# openSX70_ALPHA_V6-2-4-20181127.net
KiCad netlist of a schematic drawn in EAGLE
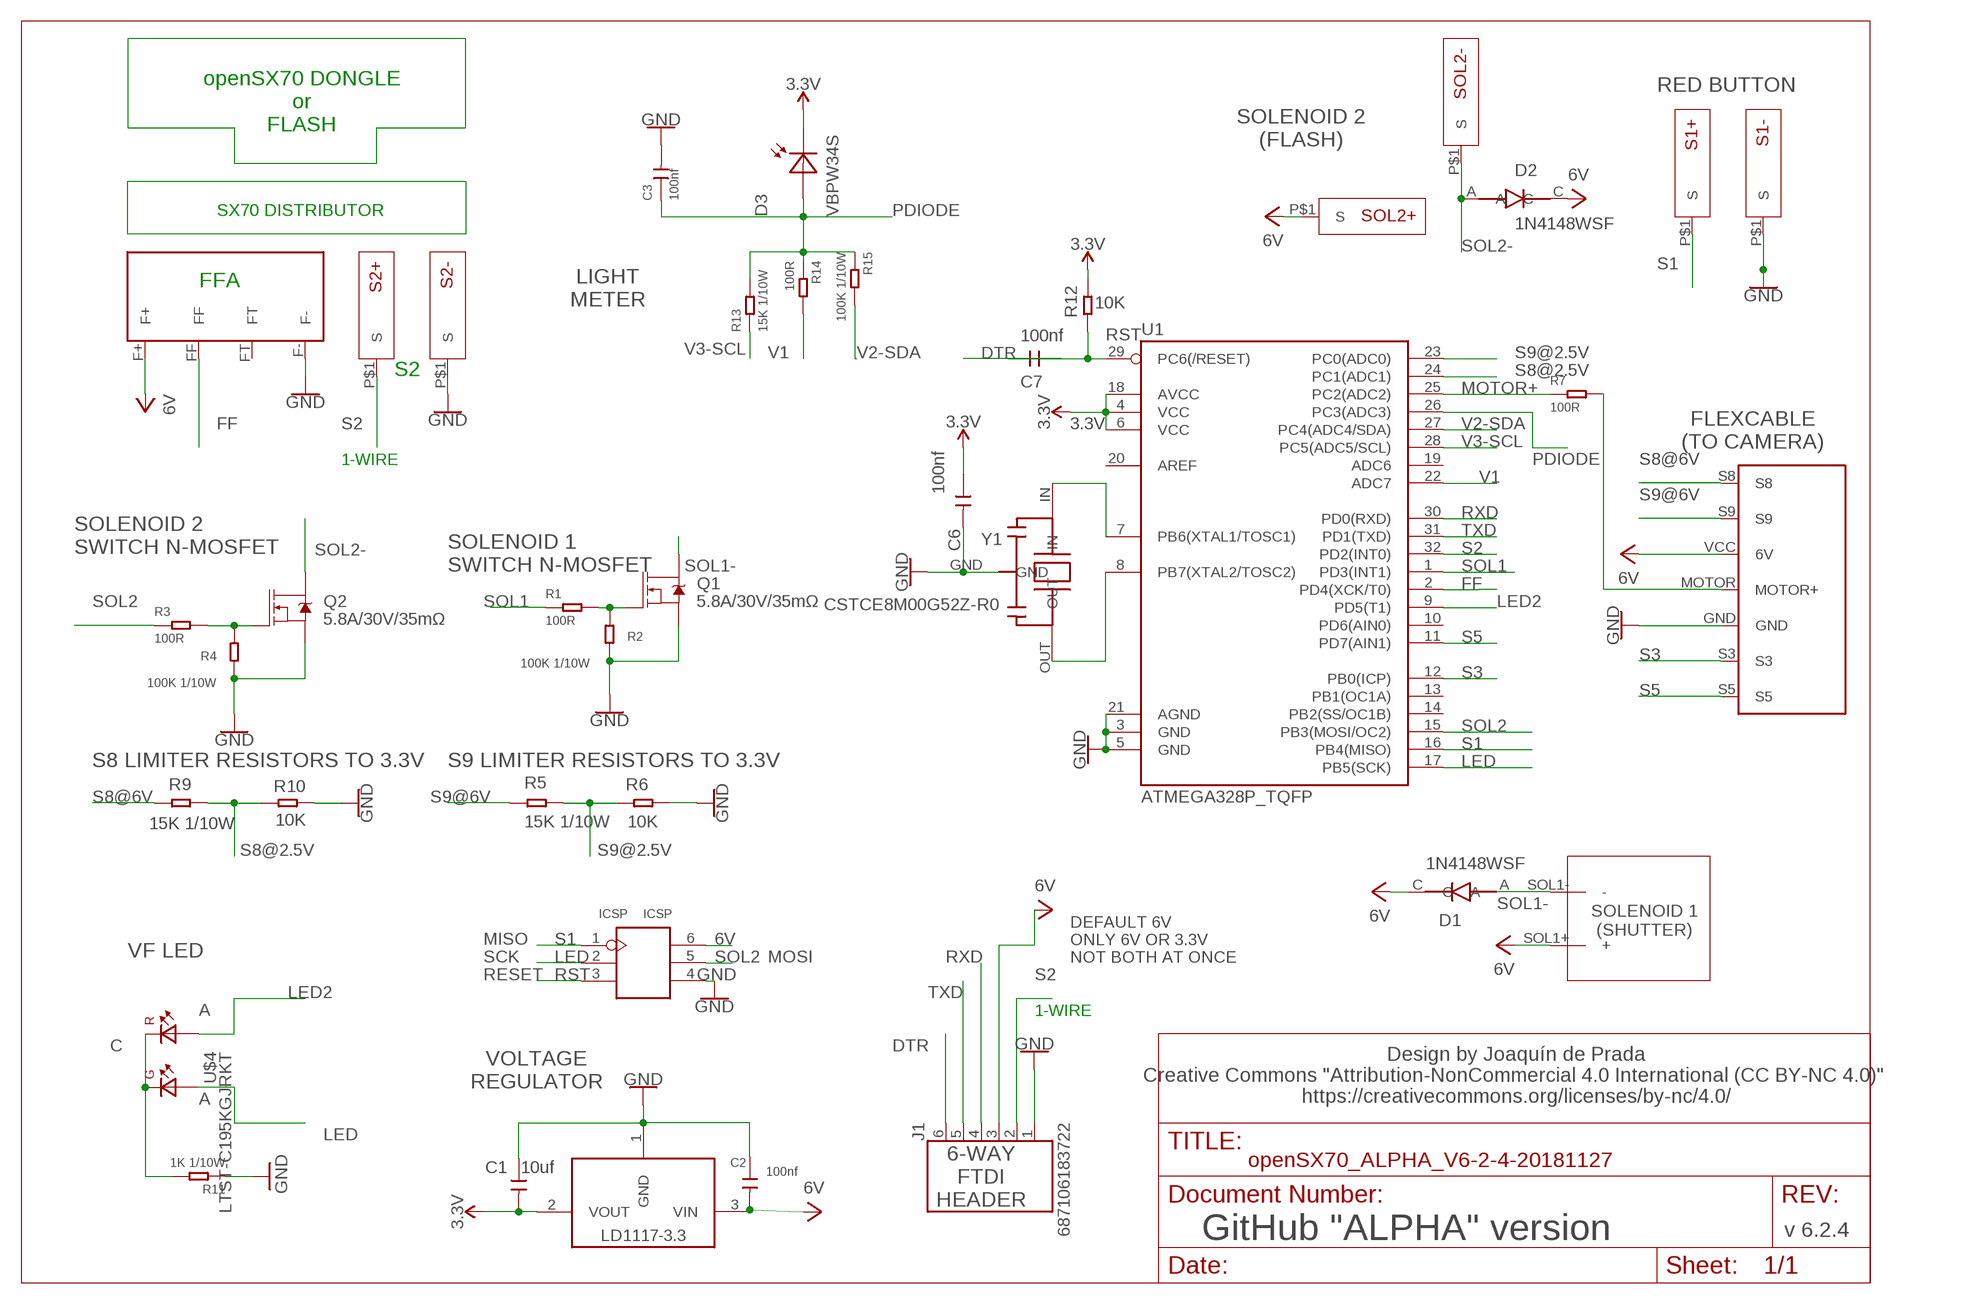
[diagram p0: schematic, sheet 1]

(export (version "E")
  (design (tool "Eeschema 10.0.6"))
  (components
    (comp (ref "C1")
      (value "10uf")
      (footprint "eagle-import:C0603")
      (fields (field (name "MPN") "CC0603KRX5R6BB106"))
      (libsource (lib "eagle-import") (part "CERAMIC-10UF-10V-10%-X5R(0603)"))
    )
    (comp (ref "C2")
      (value "100nf")
      (footprint "eagle-import:C0603")
      (fields (field (name "MPN") "CC0603KRX7R9BB104"))
      (libsource (lib "eagle-import") (part "CERAMIC-100NF-50V-10%-X7R(0603)"))
    )
    (comp (ref "C3")
      (value "100nf")
      (footprint "eagle-import:C0603")
      (fields (field (name "MPN") "CC0603KRX7R9BB104"))
      (libsource (lib "eagle-import") (part "CERAMIC-100NF-50V-10%-X7R(0603)"))
    )
    (comp (ref "C6")
      (value "100nf")
      (footprint "eagle-import:C0603")
      (fields (field (name "MPN") "CC0603KRX7R9BB104"))
      (libsource (lib "eagle-import") (part "CERAMIC-100NF-50V-10%-X7R(0603)"))
    )
    (comp (ref "C7")
      (value "100nf")
      (footprint "eagle-import:C0603")
      (fields (field (name "MPN") "CC0603KRX7R9BB104"))
      (libsource (lib "eagle-import") (part "CERAMIC-100NF-50V-10%-X7R(0603)"))
    )
    (comp (ref "D1")
      (value "1N4148WSF")
      (footprint "eagle-import:SODFL2512X100N")
      (fields (field (name "MANUFACTURER") "Fairchild Semiconductor"))
      (libsource (lib "eagle-import") (part "1N4148WS"))
    )
    (comp (ref "D2")
      (value "1N4148WSF")
      (footprint "eagle-import:SODFL2512X100N")
      (fields (field (name "MANUFACTURER") "Fairchild Semiconductor"))
      (libsource (lib "eagle-import") (part "1N4148WS"))
    )
    (comp (ref "D3")
      (value "VBPW34S")
      (footprint "eagle-import:SOD6439X130N")
      (fields (field (name "DIGI-KEY_PART_NUMBER") "751-1500-1-ND") (field (name "MF") "Vishay"))
      (libsource (lib "eagle-import") (part "VBPW34S"))
    )
    (comp (ref "ICSP")
      (value "ICSP")
      (footprint "eagle-import:H2X3-2.54")
      (libsource (lib "eagle-import") (part "ICSP"))
    )
    (comp (ref "J1")
      (value "687106183722")
      (footprint "eagle-import:687106183722")
      (fields (field (name "MF") "Wurth Electronics"))
      (libsource (lib "eagle-import") (part "687106183722"))
    )
    (comp (ref "LD11172.5V")
      (value "LD1117 2.5V")
      (footprint "eagle-import:SOT223")
      (fields (field (name "MF") "Advanced Monolithic Systems") (field (name "MP") "AMS1117-5.0"))
      (libsource (lib "eagle-import") (part "LD1117-3.3"))
    )
    (comp (ref "Q1")
      (value "5.8A/30V/35mΩ")
      (footprint "eagle-import:SOT23-3")
      (libsource (lib "eagle-import") (part "MOSFET-NCH-AO3404A"))
    )
    (comp (ref "Q2")
      (value "5.8A/30V/35mΩ")
      (footprint "eagle-import:SOT23-3")
      (libsource (lib "eagle-import") (part "MOSFET-NCH-AO3404A"))
    )
    (comp (ref "R1")
      (value "100R")
      (footprint "eagle-import:R0603")
      (fields (field (name "MPN") "RC0603JR-07100RL"))
      (libsource (lib "eagle-import") (part "SMD-RES-100R-5%-1/10W(0603)"))
    )
    (comp (ref "R2")
      (value "100K 1/10W")
      (footprint "eagle-import:R0603")
      (fields (field (name "MPN") "RC0603JR-07100KL"))
      (libsource (lib "eagle-import") (part "SMD-RES-100K-5%-1/10W(0603)"))
    )
    (comp (ref "R3")
      (value "100R")
      (footprint "eagle-import:R0603")
      (fields (field (name "MPN") "RC0603JR-07100RL"))
      (libsource (lib "eagle-import") (part "SMD-RES-100R-5%-1/10W(0603)"))
    )
    (comp (ref "R4")
      (value "100K 1/10W")
      (footprint "eagle-import:R0603")
      (fields (field (name "MPN") "RC0603JR-07100KL"))
      (libsource (lib "eagle-import") (part "SMD-RES-100K-5%-1/10W(0603)"))
    )
    (comp (ref "R5")
      (value "15K 1/10W")
      (footprint "eagle-import:R0603")
      (fields (field (name "MPN") "RC0603FR-0715KL"))
      (libsource (lib "eagle-import") (part "SMD-RES-15K-1%-1/10W(0603)"))
    )
    (comp (ref "R6")
      (value "10K")
      (footprint "eagle-import:R0603")
      (fields (field (name "MPN") "RC0603FR-0710KL"))
      (libsource (lib "eagle-import") (part "SMD-RES-10K-1%-1/10W(0603)"))
    )
    (comp (ref "R7")
      (value "100R")
      (footprint "eagle-import:R0603")
      (fields (field (name "MPN") "RC0603JR-07100RL"))
      (libsource (lib "eagle-import") (part "SMD-RES-100R-5%-1/10W(0603)"))
    )
    (comp (ref "R9")
      (value "15K 1/10W")
      (footprint "eagle-import:R0603")
      (fields (field (name "MPN") "RC0603FR-0715KL"))
      (libsource (lib "eagle-import") (part "SMD-RES-15K-1%-1/10W(0603)"))
    )
    (comp (ref "R10")
      (value "10K")
      (footprint "eagle-import:R0603")
      (fields (field (name "MPN") "RC0603FR-0710KL"))
      (libsource (lib "eagle-import") (part "SMD-RES-10K-1%-1/10W(0603)"))
    )
    (comp (ref "R11")
      (value "1K 1/10W")
      (footprint "eagle-import:R0603")
      (fields (field (name "MPN") "RC0603JR-071KL"))
      (libsource (lib "eagle-import") (part "SMD-RES-1K-5%-1/10W(0603)"))
    )
    (comp (ref "R12")
      (value "10K")
      (footprint "eagle-import:R0603")
      (fields (field (name "MPN") "RC0603FR-0710KL"))
      (libsource (lib "eagle-import") (part "SMD-RES-10K-1%-1/10W(0603)"))
    )
    (comp (ref "R13")
      (value "15K 1/10W")
      (footprint "eagle-import:R0603")
      (fields (field (name "MPN") "RC0603FR-0715KL"))
      (libsource (lib "eagle-import") (part "SMD-RES-15K-1%-1/10W(0603)"))
    )
    (comp (ref "R14")
      (value "100R")
      (footprint "eagle-import:R0603")
      (fields (field (name "MPN") "RC0603JR-07100RL"))
      (libsource (lib "eagle-import") (part "SMD-RES-100R-5%-1/10W(0603)"))
    )
    (comp (ref "R15")
      (value "100K 1/10W")
      (footprint "eagle-import:R0603")
      (fields (field (name "MPN") "RC0603JR-07100KL"))
      (libsource (lib "eagle-import") (part "SMD-RES-100K-5%-1/10W(0603)"))
    )
    (comp (ref "S1+")
      (value "SX70-S-PAD-NEW")
      (footprint "eagle-import:SX70-S-PAD2")
      (libsource (lib "eagle-import") (part "SX70-S-PAD-NEW"))
    )
    (comp (ref "S1-")
      (value "SX70-S-PAD-NEW")
      (footprint "eagle-import:SX70-S-PAD2")
      (libsource (lib "eagle-import") (part "SX70-S-PAD-NEW"))
    )
    (comp (ref "S2+")
      (value "SX70-S-PAD-NEW")
      (footprint "eagle-import:SX70-S-PAD2")
      (libsource (lib "eagle-import") (part "SX70-S-PAD-NEW"))
    )
    (comp (ref "S2-")
      (value "SX70-S-PAD-NEW")
      (footprint "eagle-import:SX70-S-PAD2")
      (libsource (lib "eagle-import") (part "SX70-S-PAD-NEW"))
    )
    (comp (ref "SOL1")
      (value "SX70-SOLENOID1-2PADS")
      (footprint "eagle-import:SX70-SOLENOID1-2")
      (libsource (lib "eagle-import") (part "SX70-SOLENOID1-2PADS"))
    )
    (comp (ref "SOL2+")
      (value "SX70-S-PAD-NEW")
      (footprint "eagle-import:SX70-S-PAD2")
      (libsource (lib "eagle-import") (part "SX70-S-PAD-NEW"))
    )
    (comp (ref "SOL2-")
      (value "SX70-S-PAD-NEW")
      (footprint "eagle-import:SX70-S-PAD2")
      (libsource (lib "eagle-import") (part "SX70-S-PAD-NEW"))
    )
    (comp (ref "U$1")
      (value "SX70-7-PAD")
      (footprint "eagle-import:SX70-7-PAD-PROPER")
      (libsource (lib "eagle-import") (part "SX70-7-PAD"))
    )
    (comp (ref "U$2")
      (value "FFA")
      (footprint "eagle-import:FFA-PAD-PACKAGE")
      (libsource (lib "eagle-import") (part "SX70-FFA-PAD"))
    )
    (comp (ref "U$4")
      (value "LTST-C195KGJRKT")
      (footprint "eagle-import:LTST-BILED-15X16")
      (fields (field (name "MF") "Lite-On Inc."))
      (libsource (lib "eagle-import") (part "LTST-C195KGJRKT"))
    )
    (comp (ref "U1")
      (value "ATMEGA328P_TQFP")
      (footprint "eagle-import:TQFP32-08")
      (libsource (lib "eagle-import") (part "ATMEGA328P_TQFP"))
    )
    (comp (ref "Y1")
      (value "CSTCE8M00G52Z-R0")
      (footprint "eagle-import:CFP95P160X100-3N")
      (fields (field (name "MF") "Murata") (field (name "MP") "CSTCE16M0V53-R0"))
      (libsource (lib "eagle-import") (part "CSTCE16M0V53-R0"))
    )
  )
  (nets
    (net (code "1") (name "/DTR") (class "Default")
      (node (ref "C7") (pin "1") (pinfunction "1_1") (pintype "passive"))
      (node (ref "J1") (pin "6") (pinfunction "1_6") (pintype "passive"))
    )
    (net (code "2") (name "/FF") (class "Default")
      (node (ref "U$2") (pin "FF") (pinfunction "FF_FF") (pintype "bidirectional"))
      (node (ref "U1") (pin "2") (pinfunction "PD4(XCK/T0)_2") (pintype "bidirectional"))
    )
    (net (code "3") (name "/LED") (class "Default")
      (node (ref "ICSP") (pin "2") (pinfunction "SCK_2") (pintype "bidirectional"))
      (node (ref "U$4") (pin "P$1") (pinfunction "A1_P$1") (pintype "passive"))
      (node (ref "U1") (pin "17") (pinfunction "PB5(SCK)_17") (pintype "bidirectional"))
    )
    (net (code "4") (name "/LED2") (class "Default")
      (node (ref "U$4") (pin "P$2") (pinfunction "A2_P$2") (pintype "passive"))
      (node (ref "U1") (pin "9") (pinfunction "PD5(T1)_9") (pintype "bidirectional"))
    )
    (net (code "5") (name "/MOTOR+") (class "Default")
      (node (ref "R7") (pin "1") (pinfunction "1_1") (pintype "passive"))
      (node (ref "U1") (pin "25") (pinfunction "PC2(ADC2)_25") (pintype "bidirectional"))
    )
    (net (code "6") (name "/PDIODE") (class "Default")
      (node (ref "C3") (pin "1") (pinfunction "1_1") (pintype "passive"))
      (node (ref "D3") (pin "A") (pinfunction "A_A") (pintype "passive"))
      (node (ref "R13") (pin "2") (pinfunction "2_2") (pintype "passive"))
      (node (ref "R14") (pin "1") (pinfunction "1_1") (pintype "passive"))
      (node (ref "R15") (pin "1") (pinfunction "1_1") (pintype "passive"))
      (node (ref "U1") (pin "26") (pinfunction "PC3(ADC3)_26") (pintype "bidirectional"))
    )
    (net (code "7") (name "/RST") (class "Default")
      (node (ref "C7") (pin "2") (pinfunction "2_2") (pintype "passive"))
      (node (ref "ICSP") (pin "3") (pinfunction "RST_3") (pintype "bidirectional"))
      (node (ref "R12") (pin "1") (pinfunction "1_1") (pintype "passive"))
      (node (ref "U1") (pin "29") (pinfunction "PC6(/RESET)_29") (pintype "bidirectional"))
    )
    (net (code "8") (name "/RXD") (class "Default")
      (node (ref "J1") (pin "4") (pinfunction "3_4") (pintype "passive"))
      (node (ref "U1") (pin "30") (pinfunction "PD0(RXD)_30") (pintype "bidirectional"))
    )
    (net (code "9") (name "/S1") (class "Default")
      (node (ref "ICSP") (pin "1") (pinfunction "MISO_1") (pintype "bidirectional"))
      (node (ref "S1+") (pin "P$1") (pinfunction "S_P$1") (pintype "bidirectional"))
      (node (ref "U1") (pin "16") (pinfunction "PB4(MISO)_16") (pintype "bidirectional"))
    )
    (net (code "10") (name "/S2") (class "Default")
      (node (ref "J1") (pin "2") (pinfunction "5_2") (pintype "passive"))
      (node (ref "S2+") (pin "P$1") (pinfunction "S_P$1") (pintype "bidirectional"))
      (node (ref "U1") (pin "32") (pinfunction "PD2(INT0)_32") (pintype "bidirectional"))
    )
    (net (code "11") (name "/S3") (class "Default")
      (node (ref "U$1") (pin "S3") (pinfunction "S3_S3") (pintype "bidirectional"))
      (node (ref "U1") (pin "12") (pinfunction "PB0(ICP)_12") (pintype "bidirectional"))
    )
    (net (code "12") (name "/S5") (class "Default")
      (node (ref "U$1") (pin "S5") (pinfunction "S5_S5") (pintype "bidirectional"))
      (node (ref "U1") (pin "11") (pinfunction "PD7(AIN1)_11") (pintype "bidirectional"))
    )
    (net (code "13") (name "/S8@2.5V") (class "Default")
      (node (ref "R10") (pin "1") (pinfunction "1_1") (pintype "passive"))
      (node (ref "R9") (pin "2") (pinfunction "2_2") (pintype "passive"))
      (node (ref "U1") (pin "24") (pinfunction "PC1(ADC1)_24") (pintype "bidirectional"))
    )
    (net (code "14") (name "/S8@6V") (class "Default")
      (node (ref "R9") (pin "1") (pinfunction "1_1") (pintype "passive"))
      (node (ref "U$1") (pin "S8") (pinfunction "S8_S8") (pintype "bidirectional"))
    )
    (net (code "15") (name "/S9@2.5V") (class "Default")
      (node (ref "R5") (pin "2") (pinfunction "2_2") (pintype "passive"))
      (node (ref "R6") (pin "1") (pinfunction "1_1") (pintype "passive"))
      (node (ref "U1") (pin "23") (pinfunction "PC0(ADC0)_23") (pintype "bidirectional"))
    )
    (net (code "16") (name "/S9@6V") (class "Default")
      (node (ref "R5") (pin "1") (pinfunction "1_1") (pintype "passive"))
      (node (ref "U$1") (pin "S9") (pinfunction "S9_S9") (pintype "bidirectional"))
    )
    (net (code "17") (name "/SOL1") (class "Default")
      (node (ref "R1") (pin "1") (pinfunction "1_1") (pintype "passive"))
      (node (ref "U1") (pin "1") (pinfunction "PD3(INT1)_1") (pintype "bidirectional"))
    )
    (net (code "18") (name "/SOL1-") (class "Default")
      (node (ref "D1") (pin "A") (pinfunction "A_A") (pintype "passive"))
      (node (ref "Q1") (pin "3") (pinfunction "D_3") (pintype "bidirectional"))
      (node (ref "SOL1") (pin "SOL1-") (pinfunction "-_SOL1-") (pintype "bidirectional"))
    )
    (net (code "19") (name "/SOL2") (class "Default")
      (node (ref "ICSP") (pin "5") (pinfunction "MOSI_5") (pintype "bidirectional"))
      (node (ref "R3") (pin "1") (pinfunction "1_1") (pintype "passive"))
      (node (ref "U1") (pin "15") (pinfunction "PB3(MOSI/OC2)_15") (pintype "bidirectional"))
    )
    (net (code "20") (name "/SOL2-") (class "Default")
      (node (ref "D2") (pin "A") (pinfunction "A_A") (pintype "passive"))
      (node (ref "Q2") (pin "3") (pinfunction "D_3") (pintype "bidirectional"))
      (node (ref "SOL2-") (pin "P$1") (pinfunction "S_P$1") (pintype "bidirectional"))
    )
    (net (code "21") (name "/TXD") (class "Default")
      (node (ref "J1") (pin "5") (pinfunction "2_5") (pintype "passive"))
      (node (ref "U1") (pin "31") (pinfunction "PD1(TXD)_31") (pintype "bidirectional"))
    )
    (net (code "22") (name "/V1") (class "Default")
      (node (ref "R14") (pin "2") (pinfunction "2_2") (pintype "passive"))
      (node (ref "U1") (pin "22") (pinfunction "ADC7_22") (pintype "bidirectional"))
    )
    (net (code "23") (name "/V2-SDA") (class "Default")
      (node (ref "R15") (pin "2") (pinfunction "2_2") (pintype "passive"))
      (node (ref "U1") (pin "27") (pinfunction "PC4(ADC4/SDA)_27") (pintype "bidirectional"))
    )
    (net (code "24") (name "/V3-SCL") (class "Default")
      (node (ref "R13") (pin "1") (pinfunction "1_1") (pintype "passive"))
      (node (ref "U1") (pin "28") (pinfunction "PC5(ADC5/SCL)_28") (pintype "bidirectional"))
    )
    (net (code "25") (name "3.3V") (class "Default")
      (node (ref "C1") (pin "2") (pinfunction "2_2") (pintype "passive"))
      (node (ref "C6") (pin "1") (pinfunction "1_1") (pintype "passive"))
      (node (ref "D3") (pin "C") (pinfunction "C_C") (pintype "passive"))
      (node (ref "LD11172.5V") (pin "2") (pinfunction "VOUT_2") (pintype "bidirectional"))
      (node (ref "R12") (pin "2") (pinfunction "2_2") (pintype "passive"))
      (node (ref "U1") (pin "18") (pinfunction "AVCC_18") (pintype "bidirectional"))
      (node (ref "U1") (pin "4") (pinfunction "VCC_4") (pintype "bidirectional"))
      (node (ref "U1") (pin "6") (pinfunction "VCC_6") (pintype "bidirectional"))
    )
    (net (code "26") (name "6V") (class "Default")
      (node (ref "C2") (pin "2") (pinfunction "2_2") (pintype "passive"))
      (node (ref "D1") (pin "C") (pinfunction "C_C") (pintype "passive"))
      (node (ref "D2") (pin "C") (pinfunction "C_C") (pintype "passive"))
      (node (ref "ICSP") (pin "6") (pinfunction "VCC_6") (pintype "bidirectional"))
      (node (ref "J1") (pin "3") (pinfunction "4_3") (pintype "passive"))
      (node (ref "LD11172.5V") (pin "3") (pinfunction "VIN_3") (pintype "bidirectional"))
      (node (ref "SOL1") (pin "SOL1+") (pinfunction "+_SOL1+") (pintype "bidirectional"))
      (node (ref "SOL2+") (pin "P$1") (pinfunction "S_P$1") (pintype "bidirectional"))
      (node (ref "U$1") (pin "VCC") (pinfunction "6V_VCC") (pintype "bidirectional"))
      (node (ref "U$2") (pin "F+") (pinfunction "F+_F+") (pintype "bidirectional"))
    )
    (net (code "27") (name "GND") (class "Default")
      (node (ref "C1") (pin "1") (pinfunction "1_1") (pintype "passive"))
      (node (ref "C2") (pin "1") (pinfunction "1_1") (pintype "passive"))
      (node (ref "C3") (pin "2") (pinfunction "2_2") (pintype "passive"))
      (node (ref "C6") (pin "2") (pinfunction "2_2") (pintype "passive"))
      (node (ref "ICSP") (pin "4") (pinfunction "GND_4") (pintype "bidirectional"))
      (node (ref "J1") (pin "1") (pinfunction "6_1") (pintype "passive"))
      (node (ref "LD11172.5V") (pin "1") (pinfunction "GND_1") (pintype "bidirectional"))
      (node (ref "Q1") (pin "2") (pinfunction "S_2") (pintype "bidirectional"))
      (node (ref "Q2") (pin "2") (pinfunction "S_2") (pintype "bidirectional"))
      (node (ref "R10") (pin "2") (pinfunction "2_2") (pintype "passive"))
      (node (ref "R11") (pin "1") (pinfunction "1_1") (pintype "passive"))
      (node (ref "R2") (pin "1") (pinfunction "1_1") (pintype "passive"))
      (node (ref "R4") (pin "1") (pinfunction "1_1") (pintype "passive"))
      (node (ref "R6") (pin "2") (pinfunction "2_2") (pintype "passive"))
      (node (ref "S1-") (pin "P$1") (pinfunction "S_P$1") (pintype "bidirectional"))
      (node (ref "S2-") (pin "P$1") (pinfunction "S_P$1") (pintype "bidirectional"))
      (node (ref "U$1") (pin "GND") (pinfunction "GND_GND") (pintype "bidirectional"))
      (node (ref "U$2") (pin "F-") (pinfunction "F-_F-") (pintype "bidirectional"))
      (node (ref "U1") (pin "21") (pinfunction "AGND_21") (pintype "bidirectional"))
      (node (ref "U1") (pin "3") (pinfunction "GND_3") (pintype "bidirectional"))
      (node (ref "U1") (pin "5") (pinfunction "GND_5") (pintype "bidirectional"))
      (node (ref "Y1") (pin "GND") (pinfunction "GND_GND") (pintype "passive"))
    )
    (net (code "28") (name "Net-(Q1-G)") (class "Default")
      (node (ref "Q1") (pin "1") (pinfunction "G_1") (pintype "bidirectional"))
      (node (ref "R1") (pin "2") (pinfunction "2_2") (pintype "passive"))
      (node (ref "R2") (pin "2") (pinfunction "2_2") (pintype "passive"))
    )
    (net (code "29") (name "Net-(Q2-G)") (class "Default")
      (node (ref "Q2") (pin "1") (pinfunction "G_1") (pintype "bidirectional"))
      (node (ref "R3") (pin "2") (pinfunction "2_2") (pintype "passive"))
      (node (ref "R4") (pin "2") (pinfunction "2_2") (pintype "passive"))
    )
    (net (code "30") (name "Net-(U$1-MOTOR+)") (class "Default")
      (node (ref "R7") (pin "2") (pinfunction "2_2") (pintype "passive"))
      (node (ref "U$1") (pin "MOTOR") (pinfunction "MOTOR+_MOTOR") (pintype "bidirectional"))
    )
    (net (code "31") (name "Net-(U$4-K1)") (class "Default")
      (node (ref "R11") (pin "2") (pinfunction "2_2") (pintype "passive"))
      (node (ref "U$4") (pin "P$3") (pinfunction "K1_P$3") (pintype "passive"))
      (node (ref "U$4") (pin "P$4") (pinfunction "K2_P$4") (pintype "passive"))
    )
    (net (code "32") (name "Net-(U1-PB6(XTAL1{slash}TOSC1))") (class "Default")
      (node (ref "U1") (pin "7") (pinfunction "PB6(XTAL1/TOSC1)_7") (pintype "bidirectional"))
      (node (ref "Y1") (pin "IN") (pinfunction "IN_IN") (pintype "input"))
    )
    (net (code "33") (name "Net-(U1-PB7(XTAL2{slash}TOSC2))") (class "Default")
      (node (ref "U1") (pin "8") (pinfunction "PB7(XTAL2/TOSC2)_8") (pintype "bidirectional"))
      (node (ref "Y1") (pin "OUT") (pinfunction "OUT_OUT") (pintype "output"))
    )
    (net (code "34") (name "unconnected-(U$2-PadFT)") (class "Default")
      (node (ref "U$2") (pin "FT") (pinfunction "FT_FT") (pintype "bidirectional"))
    )
    (net (code "35") (name "unconnected-(U1-ADC6-Pad19)") (class "Default")
      (node (ref "U1") (pin "19") (pinfunction "ADC6_19") (pintype "bidirectional"))
    )
    (net (code "36") (name "unconnected-(U1-AREF-Pad20)") (class "Default")
      (node (ref "U1") (pin "20") (pinfunction "AREF_20") (pintype "bidirectional"))
    )
    (net (code "37") (name "unconnected-(U1-PB1(OC1A)-Pad13)") (class "Default")
      (node (ref "U1") (pin "13") (pinfunction "PB1(OC1A)_13") (pintype "bidirectional"))
    )
    (net (code "38") (name "unconnected-(U1-PB2(SS{slash}OC1B)-Pad14)") (class "Default")
      (node (ref "U1") (pin "14") (pinfunction "PB2(SS/OC1B)_14") (pintype "bidirectional"))
    )
    (net (code "39") (name "unconnected-(U1-PD6(AIN0)-Pad10)") (class "Default")
      (node (ref "U1") (pin "10") (pinfunction "PD6(AIN0)_10") (pintype "bidirectional"))
    )
  )
)
